# Quadcopter.net
KiCad netlist of a schematic drawn in EAGLE
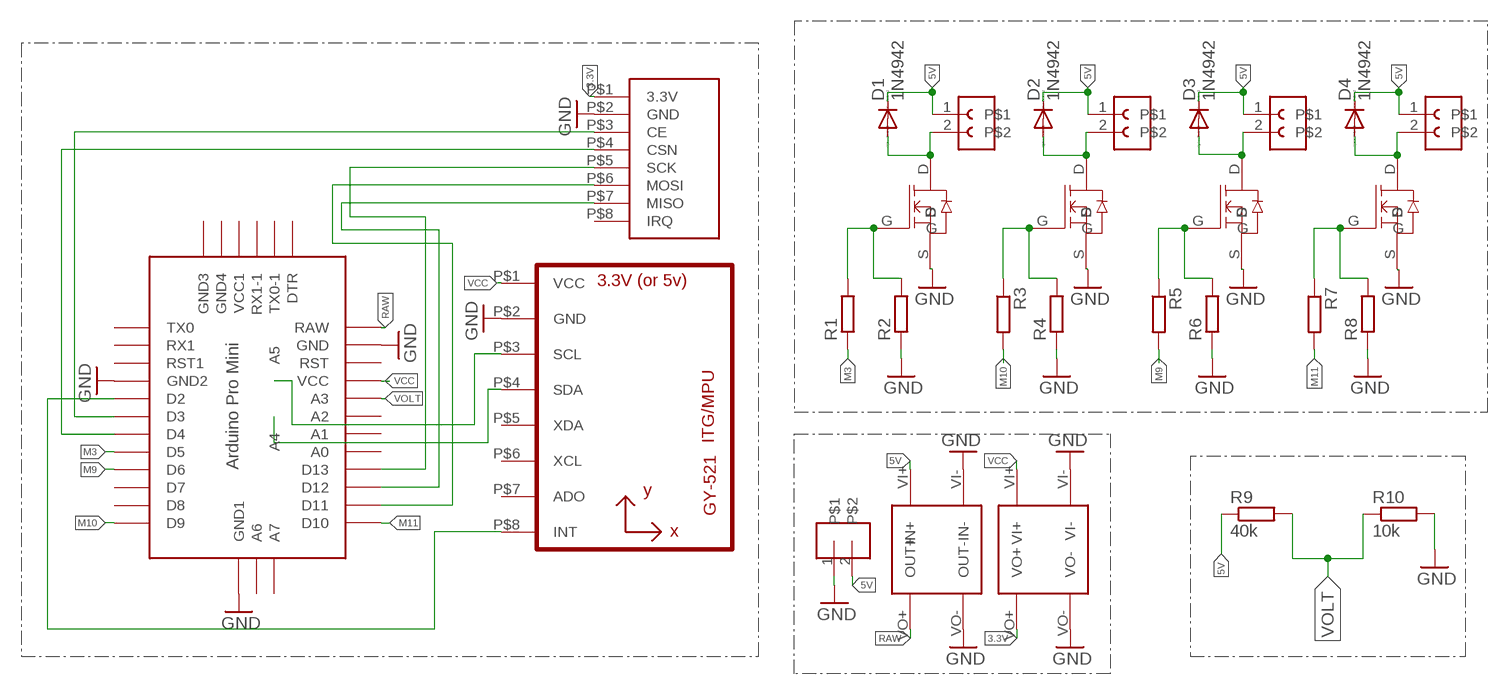
[diagram p0: schematic, sheet 1]

(export (version "E")
  (design (tool "Eeschema 10.0.6"))
  (components
    (comp (ref "D1")
      (value "1N4942")
      (footprint "eagle-import:DO41-10")
      (libsource (lib "eagle-import") (part "1N4942"))
    )
    (comp (ref "D2")
      (value "1N4942")
      (footprint "eagle-import:DO41-10")
      (libsource (lib "eagle-import") (part "1N4942"))
    )
    (comp (ref "D3")
      (value "1N4942")
      (footprint "eagle-import:DO41-10")
      (libsource (lib "eagle-import") (part "1N4942"))
    )
    (comp (ref "D4")
      (value "1N4942")
      (footprint "eagle-import:DO41-10")
      (libsource (lib "eagle-import") (part "1N4942"))
    )
    (comp (ref "R1")
      (value "R-EU_R1206")
      (footprint "eagle-import:R1206")
      (libsource (lib "eagle-import") (part "R-EU_R1206"))
    )
    (comp (ref "R2")
      (value "R-EU_R1206")
      (footprint "eagle-import:R1206")
      (libsource (lib "eagle-import") (part "R-EU_R1206"))
    )
    (comp (ref "R3")
      (value "R-EU_R1206")
      (footprint "eagle-import:R1206")
      (libsource (lib "eagle-import") (part "R-EU_R1206"))
    )
    (comp (ref "R4")
      (value "R-EU_R1206")
      (footprint "eagle-import:R1206")
      (libsource (lib "eagle-import") (part "R-EU_R1206"))
    )
    (comp (ref "R5")
      (value "R-EU_R1206")
      (footprint "eagle-import:R1206")
      (libsource (lib "eagle-import") (part "R-EU_R1206"))
    )
    (comp (ref "R6")
      (value "R-EU_R1206")
      (footprint "eagle-import:R1206")
      (libsource (lib "eagle-import") (part "R-EU_R1206"))
    )
    (comp (ref "R7")
      (value "R-EU_R1206")
      (footprint "eagle-import:R1206")
      (libsource (lib "eagle-import") (part "R-EU_R1206"))
    )
    (comp (ref "R8")
      (value "R-EU_R1206")
      (footprint "eagle-import:R1206")
      (libsource (lib "eagle-import") (part "R-EU_R1206"))
    )
    (comp (ref "R9")
      (value "40k")
      (footprint "eagle-import:R1206")
      (libsource (lib "eagle-import") (part "R-EU_R1206"))
    )
    (comp (ref "R10")
      (value "10k")
      (footprint "eagle-import:R1206")
      (libsource (lib "eagle-import") (part "R-EU_R1206"))
    )
    (comp (ref "U$1")
      (value "FE02")
      (footprint "eagle-import:FE02")
      (libsource (lib "eagle-import") (part "FE02"))
    )
    (comp (ref "U$2")
      (value "FE02")
      (footprint "eagle-import:FE02")
      (libsource (lib "eagle-import") (part "FE02"))
    )
    (comp (ref "U$3")
      (value "FE02")
      (footprint "eagle-import:FE02")
      (libsource (lib "eagle-import") (part "FE02"))
    )
    (comp (ref "U$4")
      (value "ABK-PRO-MINI")
      (footprint "eagle-import:ABK-PRO-MINI")
      (libsource (lib "eagle-import") (part "ABK-PRO-MINI"))
    )
    (comp (ref "U$5")
      (value "SI2306")
      (footprint "eagle-import:SI2306")
      (libsource (lib "eagle-import") (part "SI2306"))
    )
    (comp (ref "U$6")
      (value "02")
      (footprint "eagle-import:FE05-1")
      (libsource (lib "eagle-import") (part "02"))
    )
    (comp (ref "U$7")
      (value "SI2306")
      (footprint "eagle-import:SI2306")
      (libsource (lib "eagle-import") (part "SI2306"))
    )
    (comp (ref "U$8")
      (value "SI2306")
      (footprint "eagle-import:SI2306")
      (libsource (lib "eagle-import") (part "SI2306"))
    )
    (comp (ref "U$9")
      (value "FE02")
      (footprint "eagle-import:FE02")
      (libsource (lib "eagle-import") (part "FE02"))
    )
    (comp (ref "U$10")
      (value "SI2306")
      (footprint "eagle-import:SI2306")
      (libsource (lib "eagle-import") (part "SI2306"))
    )
    (comp (ref "U$11")
      (value "NRF24L01")
      (footprint "eagle-import:NRF24L01")
      (libsource (lib "eagle-import") (part "NRF24L01"))
    )
    (comp (ref "U$12")
      (value "3.3V")
      (footprint "eagle-import:3.3V")
      (libsource (lib "eagle-import") (part "3.3V"))
    )
    (comp (ref "U$13")
      (value "5V")
      (footprint "eagle-import:5V")
      (libsource (lib "eagle-import") (part "5V"))
    )
    (comp (ref "U2")
      (value "GY-521MPU6050")
      (footprint "eagle-import:GY-521")
      (libsource (lib "eagle-import") (part "GY-521MPU6050"))
    )
  )
  (nets
    (net (code "1") (name "3.3V") (class "Default")
      (node (ref "U$11") (pin "P$1") (pinfunction "3.3V_P$1") (pintype "bidirectional"))
      (node (ref "U$12") (pin "VO+") (pinfunction "VO+_VO+") (pintype "bidirectional"))
    )
    (net (code "2") (name "5V") (class "Default")
      (node (ref "D1") (pin "C") (pinfunction "C_C") (pintype "passive"))
      (node (ref "D2") (pin "C") (pinfunction "C_C") (pintype "passive"))
      (node (ref "D3") (pin "C") (pinfunction "C_C") (pintype "passive"))
      (node (ref "D4") (pin "C") (pinfunction "C_C") (pintype "passive"))
      (node (ref "R9") (pin "1") (pinfunction "1_1") (pintype "passive"))
      (node (ref "U$1") (pin "1") (pinfunction "P$1_1") (pintype "bidirectional"))
      (node (ref "U$13") (pin "VI+") (pinfunction "IN+_VI+") (pintype "bidirectional"))
      (node (ref "U$2") (pin "1") (pinfunction "P$1_1") (pintype "bidirectional"))
      (node (ref "U$3") (pin "1") (pinfunction "P$1_1") (pintype "bidirectional"))
      (node (ref "U$6") (pin "2") (pinfunction "P$2_2") (pintype "bidirectional"))
      (node (ref "U$9") (pin "1") (pinfunction "P$1_1") (pintype "bidirectional"))
    )
    (net (code "3") (name "GND") (class "Default")
      (node (ref "R10") (pin "2") (pinfunction "2_2") (pintype "passive"))
      (node (ref "R2") (pin "1") (pinfunction "1_1") (pintype "passive"))
      (node (ref "R4") (pin "1") (pinfunction "1_1") (pintype "passive"))
      (node (ref "R6") (pin "1") (pinfunction "1_1") (pintype "passive"))
      (node (ref "R8") (pin "1") (pinfunction "1_1") (pintype "passive"))
      (node (ref "U$10") (pin "S") (pinfunction "S_S") (pintype "bidirectional"))
      (node (ref "U$11") (pin "P$2") (pinfunction "GND_P$2") (pintype "bidirectional"))
      (node (ref "U$12") (pin "VI-") (pinfunction "VI-_VI-") (pintype "bidirectional"))
      (node (ref "U$12") (pin "VO-") (pinfunction "VO-_VO-") (pintype "bidirectional"))
      (node (ref "U$13") (pin "VI-") (pinfunction "IN-_VI-") (pintype "bidirectional"))
      (node (ref "U$13") (pin "VO-") (pinfunction "OUT-_VO-") (pintype "bidirectional"))
      (node (ref "U$4") (pin "P$10") (pinfunction "GND2_P$10") (pintype "bidirectional"))
      (node (ref "U$4") (pin "P$20") (pinfunction "GND_P$20") (pintype "bidirectional"))
      (node (ref "U$4") (pin "P$33") (pinfunction "GND1_P$33") (pintype "bidirectional"))
      (node (ref "U$5") (pin "S") (pinfunction "S_S") (pintype "bidirectional"))
      (node (ref "U$6") (pin "1") (pinfunction "P$1_1") (pintype "bidirectional"))
      (node (ref "U$7") (pin "S") (pinfunction "S_S") (pintype "bidirectional"))
      (node (ref "U$8") (pin "S") (pinfunction "S_S") (pintype "bidirectional"))
      (node (ref "U2") (pin "P$2") (pinfunction "GND_P$2") (pintype "bidirectional"))
    )
    (net (code "4") (name "M3") (class "Default")
      (node (ref "R1") (pin "1") (pinfunction "1_1") (pintype "passive"))
      (node (ref "U$4") (pin "P$14") (pinfunction "D5_P$14") (pintype "bidirectional"))
    )
    (net (code "5") (name "M9") (class "Default")
      (node (ref "R5") (pin "2") (pinfunction "2_2") (pintype "passive"))
      (node (ref "U$4") (pin "P$15") (pinfunction "D6_P$15") (pintype "bidirectional"))
    )
    (net (code "6") (name "M10") (class "Default")
      (node (ref "R3") (pin "2") (pinfunction "2_2") (pintype "passive"))
      (node (ref "U$4") (pin "P$18") (pinfunction "D9_P$18") (pintype "bidirectional"))
    )
    (net (code "7") (name "M11") (class "Default")
      (node (ref "R7") (pin "2") (pinfunction "2_2") (pintype "passive"))
      (node (ref "U$4") (pin "P$30") (pinfunction "D10_P$30") (pintype "bidirectional"))
    )
    (net (code "8") (name "Net-(R1-Pad2)") (class "Default")
      (node (ref "R1") (pin "2") (pinfunction "2_2") (pintype "passive"))
      (node (ref "R2") (pin "2") (pinfunction "2_2") (pintype "passive"))
      (node (ref "U$7") (pin "G") (pinfunction "G_G") (pintype "bidirectional"))
    )
    (net (code "9") (name "Net-(R3-Pad1)") (class "Default")
      (node (ref "R3") (pin "1") (pinfunction "1_1") (pintype "passive"))
      (node (ref "R4") (pin "2") (pinfunction "2_2") (pintype "passive"))
      (node (ref "U$8") (pin "G") (pinfunction "G_G") (pintype "bidirectional"))
    )
    (net (code "10") (name "Net-(R5-Pad1)") (class "Default")
      (node (ref "R5") (pin "1") (pinfunction "1_1") (pintype "passive"))
      (node (ref "R6") (pin "2") (pinfunction "2_2") (pintype "passive"))
      (node (ref "U$10") (pin "G") (pinfunction "G_G") (pintype "bidirectional"))
    )
    (net (code "11") (name "Net-(R7-Pad1)") (class "Default")
      (node (ref "R7") (pin "1") (pinfunction "1_1") (pintype "passive"))
      (node (ref "R8") (pin "2") (pinfunction "2_2") (pintype "passive"))
      (node (ref "U$5") (pin "G") (pinfunction "G_G") (pintype "bidirectional"))
    )
    (net (code "12") (name "Net-(U$1-P$2)") (class "Default")
      (node (ref "D2") (pin "A") (pinfunction "A_A") (pintype "passive"))
      (node (ref "U$1") (pin "2") (pinfunction "P$2_2") (pintype "bidirectional"))
      (node (ref "U$8") (pin "D") (pinfunction "D_D") (pintype "bidirectional"))
    )
    (net (code "13") (name "Net-(U$2-P$2)") (class "Default")
      (node (ref "D4") (pin "A") (pinfunction "A_A") (pintype "passive"))
      (node (ref "U$2") (pin "2") (pinfunction "P$2_2") (pintype "bidirectional"))
      (node (ref "U$5") (pin "D") (pinfunction "D_D") (pintype "bidirectional"))
    )
    (net (code "14") (name "Net-(U$3-P$2)") (class "Default")
      (node (ref "D1") (pin "A") (pinfunction "A_A") (pintype "passive"))
      (node (ref "U$3") (pin "2") (pinfunction "P$2_2") (pintype "bidirectional"))
      (node (ref "U$7") (pin "D") (pinfunction "D_D") (pintype "bidirectional"))
    )
    (net (code "15") (name "Net-(U$4-A4)") (class "Default")
      (node (ref "U$4") (pin "P$35") (pinfunction "A4_P$35") (pintype "bidirectional"))
      (node (ref "U2") (pin "P$4") (pinfunction "SDA_P$4") (pintype "bidirectional"))
    )
    (net (code "16") (name "Net-(U$4-A5)") (class "Default")
      (node (ref "U$4") (pin "P$34") (pinfunction "A5_P$34") (pintype "bidirectional"))
      (node (ref "U2") (pin "P$3") (pinfunction "SCL_P$3") (pintype "bidirectional"))
    )
    (net (code "17") (name "Net-(U$4-D2)") (class "Default")
      (node (ref "U$4") (pin "P$11") (pinfunction "D2_P$11") (pintype "bidirectional"))
      (node (ref "U2") (pin "P$8") (pinfunction "INT_P$8") (pintype "bidirectional"))
    )
    (net (code "18") (name "Net-(U$9-P$2)") (class "Default")
      (node (ref "D3") (pin "A") (pinfunction "A_A") (pintype "passive"))
      (node (ref "U$10") (pin "D") (pinfunction "D_D") (pintype "bidirectional"))
      (node (ref "U$9") (pin "2") (pinfunction "P$2_2") (pintype "bidirectional"))
    )
    (net (code "19") (name "Net-(U$11-CE)") (class "Default")
      (node (ref "U$11") (pin "P$3") (pinfunction "CE_P$3") (pintype "bidirectional"))
      (node (ref "U$4") (pin "P$12") (pinfunction "D3_P$12") (pintype "bidirectional"))
    )
    (net (code "20") (name "Net-(U$11-CSN)") (class "Default")
      (node (ref "U$11") (pin "P$4") (pinfunction "CSN_P$4") (pintype "bidirectional"))
      (node (ref "U$4") (pin "P$13") (pinfunction "D4_P$13") (pintype "bidirectional"))
    )
    (net (code "21") (name "Net-(U$11-MISO)") (class "Default")
      (node (ref "U$11") (pin "P$7") (pinfunction "MISO_P$7") (pintype "bidirectional"))
      (node (ref "U$4") (pin "P$28") (pinfunction "D12_P$28") (pintype "bidirectional"))
    )
    (net (code "22") (name "Net-(U$11-MOSI)") (class "Default")
      (node (ref "U$11") (pin "P$6") (pinfunction "MOSI_P$6") (pintype "bidirectional"))
      (node (ref "U$4") (pin "P$29") (pinfunction "D11_P$29") (pintype "bidirectional"))
    )
    (net (code "23") (name "Net-(U$11-SCK)") (class "Default")
      (node (ref "U$11") (pin "P$5") (pinfunction "SCK_P$5") (pintype "bidirectional"))
      (node (ref "U$4") (pin "P$27") (pinfunction "D13_P$27") (pintype "bidirectional"))
    )
    (net (code "24") (name "RAW") (class "Default")
      (node (ref "U$13") (pin "VO+") (pinfunction "OUT+_VO+") (pintype "bidirectional"))
      (node (ref "U$4") (pin "P$19") (pinfunction "RAW_P$19") (pintype "bidirectional"))
    )
    (net (code "25") (name "VCC") (class "Default")
      (node (ref "U$12") (pin "VI+") (pinfunction "VI+_VI+") (pintype "bidirectional"))
      (node (ref "U$4") (pin "P$22") (pinfunction "VCC_P$22") (pintype "bidirectional"))
      (node (ref "U2") (pin "P$1") (pinfunction "VCC_P$1") (pintype "bidirectional"))
    )
    (net (code "26") (name "VOLT") (class "Default")
      (node (ref "R10") (pin "1") (pinfunction "1_1") (pintype "passive"))
      (node (ref "R9") (pin "2") (pinfunction "2_2") (pintype "passive"))
      (node (ref "U$4") (pin "P$23") (pinfunction "A3_P$23") (pintype "bidirectional"))
    )
    (net (code "27") (name "unconnected-(U$4-A0-PadP$26)") (class "Default")
      (node (ref "U$4") (pin "P$26") (pinfunction "A0_P$26") (pintype "bidirectional"))
    )
    (net (code "28") (name "unconnected-(U$4-A1-PadP$25)") (class "Default")
      (node (ref "U$4") (pin "P$25") (pinfunction "A1_P$25") (pintype "bidirectional"))
    )
    (net (code "29") (name "unconnected-(U$4-A2-PadP$24)") (class "Default")
      (node (ref "U$4") (pin "P$24") (pinfunction "A2_P$24") (pintype "bidirectional"))
    )
    (net (code "30") (name "unconnected-(U$4-A6-PadP$32)") (class "Default")
      (node (ref "U$4") (pin "P$32") (pinfunction "A6_P$32") (pintype "bidirectional"))
    )
    (net (code "31") (name "unconnected-(U$4-A7-PadP$31)") (class "Default")
      (node (ref "U$4") (pin "P$31") (pinfunction "A7_P$31") (pintype "bidirectional"))
    )
    (net (code "32") (name "unconnected-(U$4-D7-PadP$16)") (class "Default")
      (node (ref "U$4") (pin "P$16") (pinfunction "D7_P$16") (pintype "bidirectional"))
    )
    (net (code "33") (name "unconnected-(U$4-D8-PadP$17)") (class "Default")
      (node (ref "U$4") (pin "P$17") (pinfunction "D8_P$17") (pintype "bidirectional"))
    )
    (net (code "34") (name "unconnected-(U$4-DTR-PadP$36)") (class "Default")
      (node (ref "U$4") (pin "P$36") (pinfunction "DTR_P$36") (pintype "bidirectional"))
    )
    (net (code "35") (name "unconnected-(U$4-GND3-PadP$37)") (class "Default")
      (node (ref "U$4") (pin "P$37") (pinfunction "GND3_P$37") (pintype "bidirectional"))
    )
    (net (code "36") (name "unconnected-(U$4-GND4-PadP$38)") (class "Default")
      (node (ref "U$4") (pin "P$38") (pinfunction "GND4_P$38") (pintype "bidirectional"))
    )
    (net (code "37") (name "unconnected-(U$4-RST-PadP$21)") (class "Default")
      (node (ref "U$4") (pin "P$21") (pinfunction "RST_P$21") (pintype "bidirectional"))
    )
    (net (code "38") (name "unconnected-(U$4-RST1-PadP$9)") (class "Default")
      (node (ref "U$4") (pin "P$9") (pinfunction "RST1_P$9") (pintype "bidirectional"))
    )
    (net (code "39") (name "unconnected-(U$4-RX1-1-PadP$39)") (class "Default")
      (node (ref "U$4") (pin "P$39") (pinfunction "RX1-1_P$39") (pintype "bidirectional"))
    )
    (net (code "40") (name "unconnected-(U$4-RX1-PadP$8)") (class "Default")
      (node (ref "U$4") (pin "P$8") (pinfunction "RX1_P$8") (pintype "bidirectional"))
    )
    (net (code "41") (name "unconnected-(U$4-TX0-1-PadP$40)") (class "Default")
      (node (ref "U$4") (pin "P$40") (pinfunction "TX0-1_P$40") (pintype "bidirectional"))
    )
    (net (code "42") (name "unconnected-(U$4-TX0-PadP$7)") (class "Default")
      (node (ref "U$4") (pin "P$7") (pinfunction "TX0_P$7") (pintype "bidirectional"))
    )
    (net (code "43") (name "unconnected-(U$4-VCC1-PadP$41)") (class "Default")
      (node (ref "U$4") (pin "P$41") (pinfunction "VCC1_P$41") (pintype "bidirectional"))
    )
    (net (code "44") (name "unconnected-(U$11-IRQ-PadP$8)") (class "Default")
      (node (ref "U$11") (pin "P$8") (pinfunction "IRQ_P$8") (pintype "bidirectional"))
    )
    (net (code "45") (name "unconnected-(U2-ADO-PadP$7)") (class "Default")
      (node (ref "U2") (pin "P$7") (pinfunction "ADO_P$7") (pintype "bidirectional"))
    )
    (net (code "46") (name "unconnected-(U2-XCL-PadP$6)") (class "Default")
      (node (ref "U2") (pin "P$6") (pinfunction "XCL_P$6") (pintype "bidirectional"))
    )
    (net (code "47") (name "unconnected-(U2-XDA-PadP$5)") (class "Default")
      (node (ref "U2") (pin "P$5") (pinfunction "XDA_P$5") (pintype "bidirectional"))
    )
  )
)
